# TH555-MainBoard.net
KiCad netlist of a schematic drawn in EAGLE
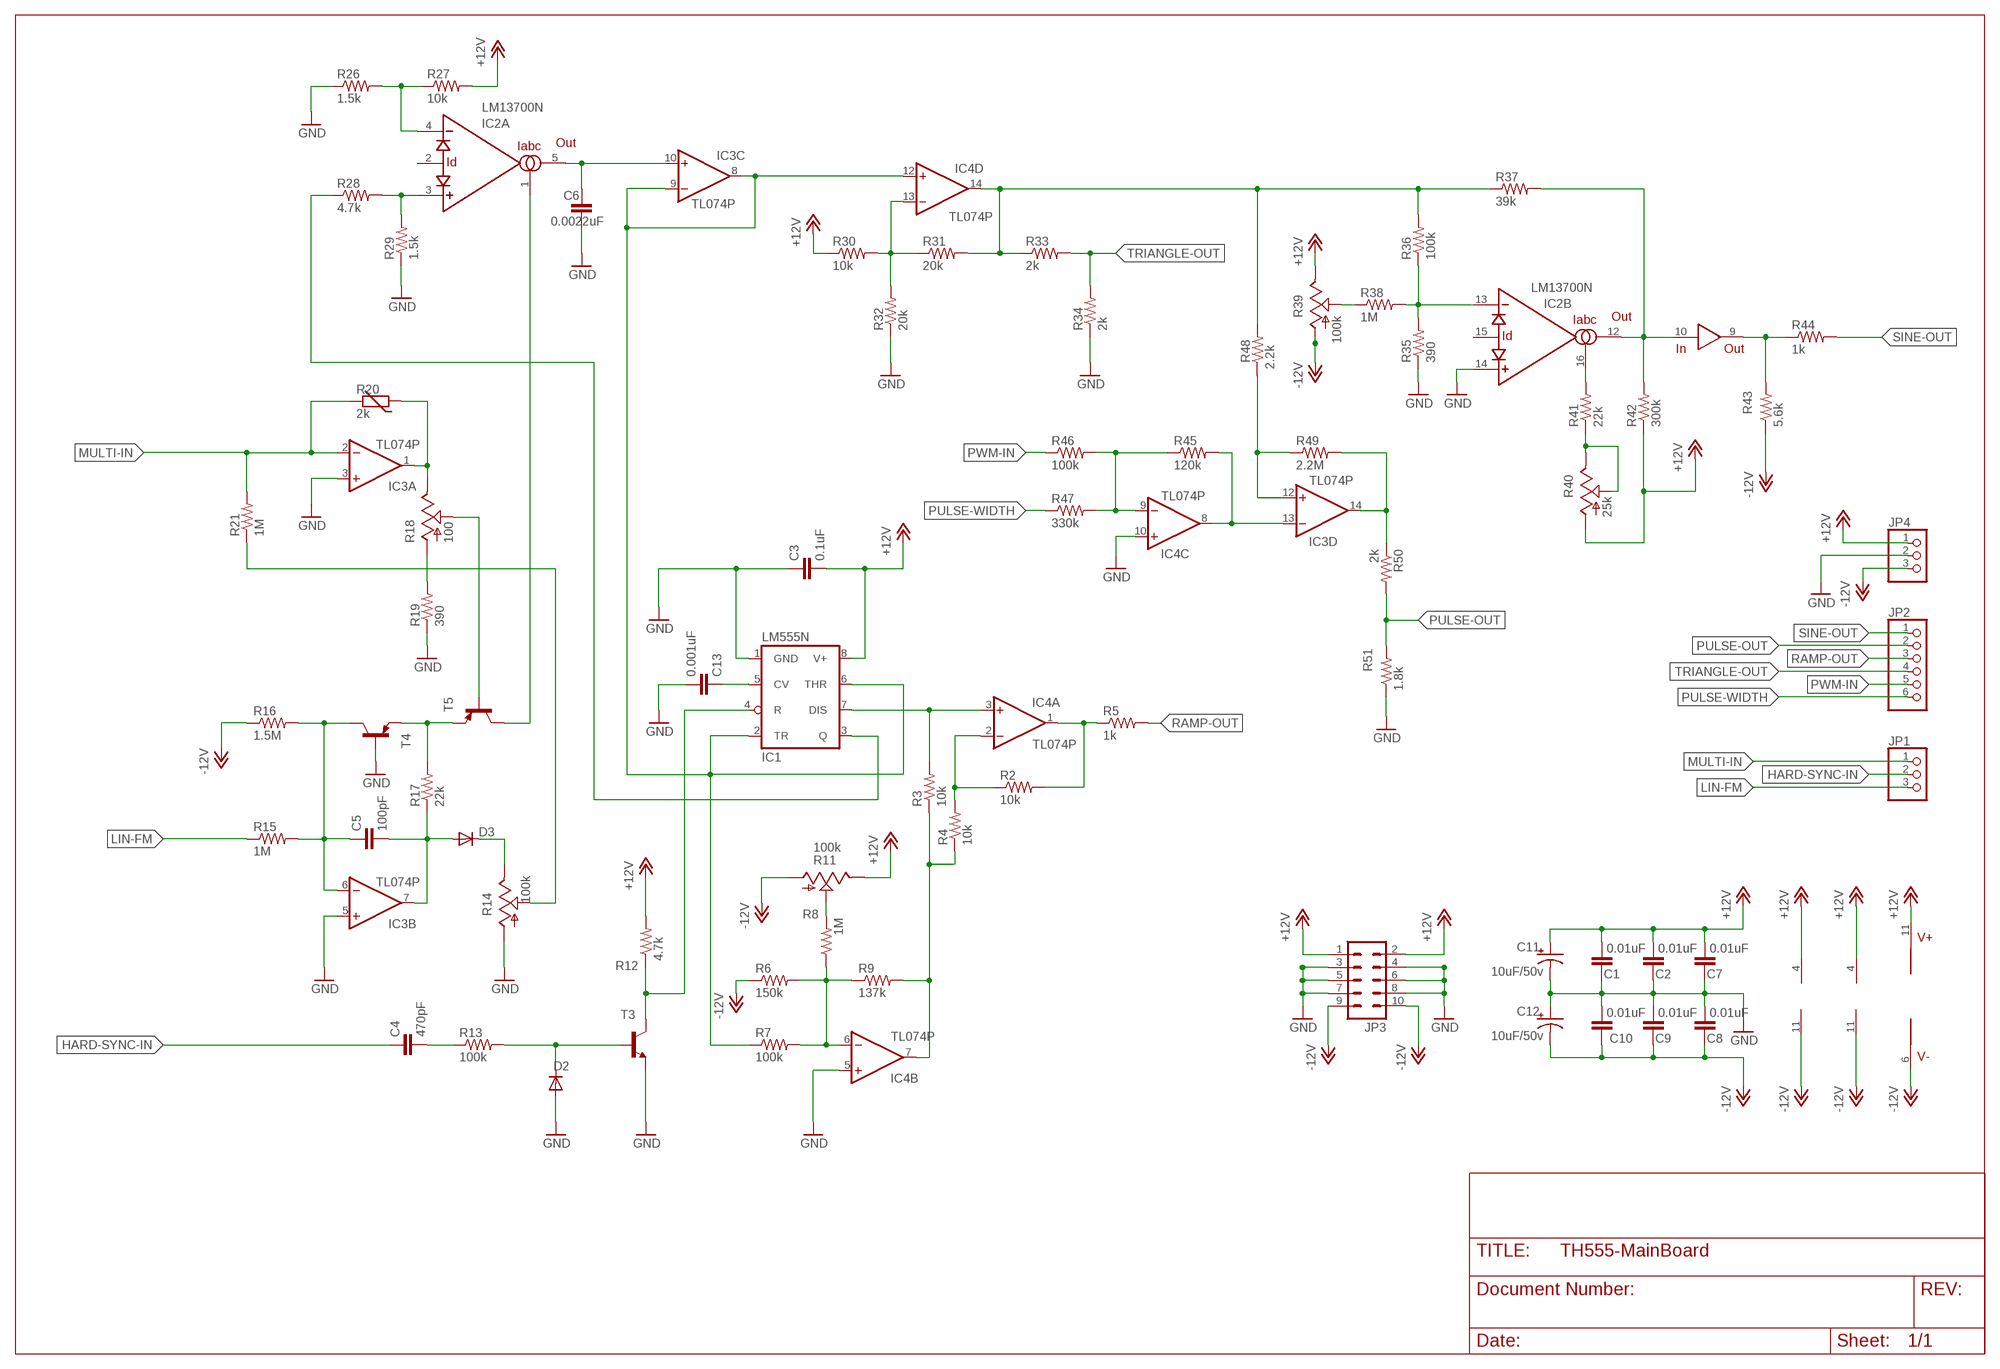
[diagram p0: schematic, sheet 1]

(export (version "E")
  (design (tool "Eeschema 10.0.6"))
  (components
    (comp (ref "C1")
      (value "0.01uF")
      (footprint "eagle-import:C050-024X044")
      (libsource (lib "eagle-import") (part "C-EU050-024X044"))
    )
    (comp (ref "C2")
      (value "0.01uF")
      (footprint "eagle-import:C050-024X044")
      (libsource (lib "eagle-import") (part "C-EU050-024X044"))
    )
    (comp (ref "C3")
      (value "0.1uF")
      (footprint "eagle-import:C050-024X044")
      (libsource (lib "eagle-import") (part "C-EU050-024X044"))
    )
    (comp (ref "C4")
      (value "470pF")
      (footprint "eagle-import:C050-024X044")
      (libsource (lib "eagle-import") (part "C-EU050-024X044"))
    )
    (comp (ref "C5")
      (value "100pF")
      (footprint "eagle-import:C050-024X044")
      (libsource (lib "eagle-import") (part "C-EU050-024X044"))
    )
    (comp (ref "C6")
      (value "0.0022uF")
      (footprint "eagle-import:C050-025X075")
      (libsource (lib "eagle-import") (part "C-EU050-025X075"))
    )
    (comp (ref "C7")
      (value "0.01uF")
      (footprint "eagle-import:C050-024X044")
      (libsource (lib "eagle-import") (part "C-EU050-024X044"))
    )
    (comp (ref "C8")
      (value "0.01uF")
      (footprint "eagle-import:C050-024X044")
      (libsource (lib "eagle-import") (part "C-EU050-024X044"))
    )
    (comp (ref "C9")
      (value "0.01uF")
      (footprint "eagle-import:C050-024X044")
      (libsource (lib "eagle-import") (part "C-EU050-024X044"))
    )
    (comp (ref "C10")
      (value "0.01uF")
      (footprint "eagle-import:C050-024X044")
      (libsource (lib "eagle-import") (part "C-EU050-024X044"))
    )
    (comp (ref "C11")
      (value "10uF/50v")
      (footprint "eagle-import:E2,5-6")
      (libsource (lib "eagle-import") (part "CPOL-USE2.5-6"))
    )
    (comp (ref "C12")
      (value "10uF/50v")
      (footprint "eagle-import:E2,5-6")
      (libsource (lib "eagle-import") (part "CPOL-USE2.5-6"))
    )
    (comp (ref "C13")
      (value "0.001uF")
      (footprint "eagle-import:C050-024X044")
      (libsource (lib "eagle-import") (part "C-EU050-024X044"))
    )
    (comp (ref "D2")
      (value "1N4148DO35-7")
      (footprint "eagle-import:DO35-7")
      (libsource (lib "eagle-import") (part "1N4148DO35-7"))
    )
    (comp (ref "D3")
      (value "1N4148DO35-7")
      (footprint "eagle-import:DO35-7")
      (libsource (lib "eagle-import") (part "1N4148DO35-7"))
    )
    (comp (ref "IC1")
      (value "LM555N")
      (footprint "eagle-import:DIL08")
      (libsource (lib "eagle-import") (part "555NLM"))
    )
    (comp (ref "IC2")
      (value "LM13700N")
      (footprint "eagle-import:DIL16")
      (libsource (lib "eagle-import") (part "LM13700N"))
    )
    (comp (ref "IC3")
      (value "TL074P")
      (footprint "eagle-import:DIL14")
      (libsource (lib "eagle-import") (part "TL074P"))
    )
    (comp (ref "IC4")
      (value "TL074P")
      (footprint "eagle-import:DIL14")
      (libsource (lib "eagle-import") (part "TL074P"))
    )
    (comp (ref "JP1")
      (value "PINHD-1X3")
      (footprint "eagle-import:1X03")
      (libsource (lib "eagle-import") (part "PINHD-1X3"))
    )
    (comp (ref "JP2")
      (value "PINHD-1X6")
      (footprint "eagle-import:1X06")
      (libsource (lib "eagle-import") (part "PINHD-1X6"))
    )
    (comp (ref "JP3")
      (value "ML10")
      (footprint "eagle-import:ML10")
      (libsource (lib "eagle-import") (part "ML10"))
    )
    (comp (ref "JP4")
      (value "PINHD-1X3")
      (footprint "eagle-import:1X03")
      (libsource (lib "eagle-import") (part "PINHD-1X3"))
    )
    (comp (ref "R2")
      (value "10k")
      (footprint "eagle-import:0204_7")
      (libsource (lib "eagle-import") (part "R-US_0204/7"))
    )
    (comp (ref "R3")
      (value "10k")
      (footprint "eagle-import:0204_7")
      (libsource (lib "eagle-import") (part "R-US_0204/7"))
    )
    (comp (ref "R4")
      (value "10k")
      (footprint "eagle-import:0204_7")
      (libsource (lib "eagle-import") (part "R-US_0204/7"))
    )
    (comp (ref "R5")
      (value "1k")
      (footprint "eagle-import:0204_7")
      (libsource (lib "eagle-import") (part "R-US_0204/7"))
    )
    (comp (ref "R6")
      (value "150k")
      (footprint "eagle-import:0204_7")
      (libsource (lib "eagle-import") (part "R-US_0204/7"))
    )
    (comp (ref "R7")
      (value "100k")
      (footprint "eagle-import:0204_7")
      (libsource (lib "eagle-import") (part "R-US_0204/7"))
    )
    (comp (ref "R8")
      (value "1M")
      (footprint "eagle-import:0204_7")
      (libsource (lib "eagle-import") (part "R-US_0204/7"))
    )
    (comp (ref "R9")
      (value "137k")
      (footprint "eagle-import:0204_7")
      (libsource (lib "eagle-import") (part "R-US_0204/7"))
    )
    (comp (ref "R11")
      (value "100k")
      (footprint "eagle-import:RJ9W")
      (libsource (lib "eagle-import") (part "TRIM_US-RJ9W"))
    )
    (comp (ref "R12")
      (value "4.7k")
      (footprint "eagle-import:0204_7")
      (libsource (lib "eagle-import") (part "R-US_0204/7"))
    )
    (comp (ref "R13")
      (value "100k")
      (footprint "eagle-import:0204_7")
      (libsource (lib "eagle-import") (part "R-US_0204/7"))
    )
    (comp (ref "R14")
      (value "100k")
      (footprint "eagle-import:RJ9W")
      (libsource (lib "eagle-import") (part "TRIM_US-RJ9W"))
    )
    (comp (ref "R15")
      (value "1M")
      (footprint "eagle-import:0204_7")
      (libsource (lib "eagle-import") (part "R-US_0204/7"))
    )
    (comp (ref "R16")
      (value "1.5M")
      (footprint "eagle-import:0204_7")
      (libsource (lib "eagle-import") (part "R-US_0204/7"))
    )
    (comp (ref "R17")
      (value "22k")
      (footprint "eagle-import:0204_7")
      (libsource (lib "eagle-import") (part "R-US_0204/7"))
    )
    (comp (ref "R18")
      (value "100")
      (footprint "eagle-import:RJ9W")
      (libsource (lib "eagle-import") (part "TRIM_US-RJ9W"))
    )
    (comp (ref "R19")
      (value "390")
      (footprint "eagle-import:0204_7")
      (libsource (lib "eagle-import") (part "R-US_0204/7"))
    )
    (comp (ref "R20")
      (value "2k")
      (footprint "eagle-import:R-5")
      (libsource (lib "eagle-import") (part "THERMISTOR-5"))
    )
    (comp (ref "R21")
      (value "1M")
      (footprint "eagle-import:0204_7")
      (libsource (lib "eagle-import") (part "R-US_0204/7"))
    )
    (comp (ref "R26")
      (value "1.5k")
      (footprint "eagle-import:0204_7")
      (libsource (lib "eagle-import") (part "R-US_0204/7"))
    )
    (comp (ref "R27")
      (value "10k")
      (footprint "eagle-import:0204_7")
      (libsource (lib "eagle-import") (part "R-US_0204/7"))
    )
    (comp (ref "R28")
      (value "4.7k")
      (footprint "eagle-import:0204_7")
      (libsource (lib "eagle-import") (part "R-US_0204/7"))
    )
    (comp (ref "R29")
      (value "1.5k")
      (footprint "eagle-import:0204_7")
      (libsource (lib "eagle-import") (part "R-US_0204/7"))
    )
    (comp (ref "R30")
      (value "10k")
      (footprint "eagle-import:0204_7")
      (libsource (lib "eagle-import") (part "R-US_0204/7"))
    )
    (comp (ref "R31")
      (value "20k")
      (footprint "eagle-import:0204_7")
      (libsource (lib "eagle-import") (part "R-US_0204/7"))
    )
    (comp (ref "R32")
      (value "20k")
      (footprint "eagle-import:0204_7")
      (libsource (lib "eagle-import") (part "R-US_0204/7"))
    )
    (comp (ref "R33")
      (value "2k")
      (footprint "eagle-import:0204_7")
      (libsource (lib "eagle-import") (part "R-US_0204/7"))
    )
    (comp (ref "R34")
      (value "2k")
      (footprint "eagle-import:0204_7")
      (libsource (lib "eagle-import") (part "R-US_0204/7"))
    )
    (comp (ref "R35")
      (value "390")
      (footprint "eagle-import:0204_7")
      (libsource (lib "eagle-import") (part "R-US_0204/7"))
    )
    (comp (ref "R36")
      (value "100k")
      (footprint "eagle-import:0204_7")
      (libsource (lib "eagle-import") (part "R-US_0204/7"))
    )
    (comp (ref "R37")
      (value "39k")
      (footprint "eagle-import:0204_7")
      (libsource (lib "eagle-import") (part "R-US_0204/7"))
    )
    (comp (ref "R38")
      (value "1M")
      (footprint "eagle-import:0204_7")
      (libsource (lib "eagle-import") (part "R-US_0204/7"))
    )
    (comp (ref "R39")
      (value "100k")
      (footprint "eagle-import:RJ9W")
      (libsource (lib "eagle-import") (part "TRIM_US-RJ9W"))
    )
    (comp (ref "R40")
      (value "25k")
      (footprint "eagle-import:RJ9W")
      (libsource (lib "eagle-import") (part "TRIM_US-RJ9W"))
    )
    (comp (ref "R41")
      (value "22k")
      (footprint "eagle-import:0204_7")
      (libsource (lib "eagle-import") (part "R-US_0204/7"))
    )
    (comp (ref "R42")
      (value "300k")
      (footprint "eagle-import:0204_7")
      (libsource (lib "eagle-import") (part "R-US_0204/7"))
    )
    (comp (ref "R43")
      (value "5.6k")
      (footprint "eagle-import:0204_7")
      (libsource (lib "eagle-import") (part "R-US_0204/7"))
    )
    (comp (ref "R44")
      (value "1k")
      (footprint "eagle-import:0204_7")
      (libsource (lib "eagle-import") (part "R-US_0204/7"))
    )
    (comp (ref "R45")
      (value "120k")
      (footprint "eagle-import:0204_7")
      (libsource (lib "eagle-import") (part "R-US_0204/7"))
    )
    (comp (ref "R46")
      (value "100k")
      (footprint "eagle-import:0204_7")
      (libsource (lib "eagle-import") (part "R-US_0204/7"))
    )
    (comp (ref "R47")
      (value "330k")
      (footprint "eagle-import:0204_7")
      (libsource (lib "eagle-import") (part "R-US_0204/7"))
    )
    (comp (ref "R48")
      (value "2.2k")
      (footprint "eagle-import:0204_7")
      (libsource (lib "eagle-import") (part "R-US_0204/7"))
    )
    (comp (ref "R49")
      (value "2.2M")
      (footprint "eagle-import:0204_7")
      (libsource (lib "eagle-import") (part "R-US_0204/7"))
    )
    (comp (ref "R50")
      (value "2k")
      (footprint "eagle-import:0204_7")
      (libsource (lib "eagle-import") (part "R-US_0204/7"))
    )
    (comp (ref "R51")
      (value "1.8k")
      (footprint "eagle-import:0204_7")
      (libsource (lib "eagle-import") (part "R-US_0204/7"))
    )
    (comp (ref "T3")
      (value "2N3904-NPN-TO92-EBC")
      (footprint "eagle-import:TO92-EBC")
      (libsource (lib "eagle-import") (part "-NPN-TO92-EBC2N3904"))
    )
    (comp (ref "T4")
      (value "2N3906-PNP-TO92-EBC")
      (footprint "eagle-import:TO92-EBC")
      (libsource (lib "eagle-import") (part "-PNP-TO92-EBC2N3906"))
    )
    (comp (ref "T5")
      (value "2N3906-PNP-TO92-EBC")
      (footprint "eagle-import:TO92-EBC")
      (libsource (lib "eagle-import") (part "-PNP-TO92-EBC2N3906"))
    )
  )
  (nets
    (net (code "1") (name "+12V") (class "Default")
      (node (ref "C1") (pin "2") (pinfunction "2_2") (pintype "passive"))
      (node (ref "C11") (pin "+") (pinfunction "+_+") (pintype "passive"))
      (node (ref "C2") (pin "2") (pinfunction "2_2") (pintype "passive"))
      (node (ref "C3") (pin "2") (pinfunction "2_2") (pintype "passive"))
      (node (ref "C7") (pin "2") (pinfunction "2_2") (pintype "passive"))
      (node (ref "IC1") (pin "8") (pinfunction "V+_8") (pintype "power_in"))
      (node (ref "IC2") (pin "11") (pinfunction "V+_11") (pintype "bidirectional"))
      (node (ref "IC3") (pin "4") (pinfunction "V+_4") (pintype "power_in"))
      (node (ref "IC4") (pin "4") (pinfunction "V+_4") (pintype "power_in"))
      (node (ref "JP3") (pin "1") (pinfunction "1_1") (pintype "passive"))
      (node (ref "JP3") (pin "2") (pinfunction "2_2") (pintype "passive"))
      (node (ref "JP4") (pin "1") (pinfunction "1_1") (pintype "passive"))
      (node (ref "R11") (pin "E") (pinfunction "E_E") (pintype "passive"))
      (node (ref "R12") (pin "2") (pinfunction "2_2") (pintype "passive"))
      (node (ref "R27") (pin "2") (pinfunction "2_2") (pintype "passive"))
      (node (ref "R30") (pin "1") (pinfunction "1_1") (pintype "passive"))
      (node (ref "R39") (pin "E") (pinfunction "E_E") (pintype "passive"))
      (node (ref "R40") (pin "A") (pinfunction "A_A") (pintype "passive"))
      (node (ref "R42") (pin "1") (pinfunction "1_1") (pintype "passive"))
    )
    (net (code "2") (name "-12V") (class "Default")
      (node (ref "C10") (pin "1") (pinfunction "1_1") (pintype "passive"))
      (node (ref "C12") (pin "-") (pinfunction "-_-") (pintype "passive"))
      (node (ref "C8") (pin "1") (pinfunction "1_1") (pintype "passive"))
      (node (ref "C9") (pin "1") (pinfunction "1_1") (pintype "passive"))
      (node (ref "IC2") (pin "6") (pinfunction "V-_6") (pintype "bidirectional"))
      (node (ref "IC3") (pin "11") (pinfunction "V-_11") (pintype "power_in"))
      (node (ref "IC4") (pin "11") (pinfunction "V-_11") (pintype "power_in"))
      (node (ref "JP3") (pin "10") (pinfunction "10_10") (pintype "passive"))
      (node (ref "JP3") (pin "9") (pinfunction "9_9") (pintype "passive"))
      (node (ref "JP4") (pin "3") (pinfunction "3_3") (pintype "passive"))
      (node (ref "R11") (pin "A") (pinfunction "A_A") (pintype "passive"))
      (node (ref "R16") (pin "1") (pinfunction "1_1") (pintype "passive"))
      (node (ref "R39") (pin "A") (pinfunction "A_A") (pintype "passive"))
      (node (ref "R43") (pin "1") (pinfunction "1_1") (pintype "passive"))
      (node (ref "R6") (pin "1") (pinfunction "1_1") (pintype "passive"))
    )
    (net (code "3") (name "GND") (class "Default")
      (node (ref "C1") (pin "1") (pinfunction "1_1") (pintype "passive"))
      (node (ref "C10") (pin "2") (pinfunction "2_2") (pintype "passive"))
      (node (ref "C11") (pin "-") (pinfunction "-_-") (pintype "passive"))
      (node (ref "C12") (pin "+") (pinfunction "+_+") (pintype "passive"))
      (node (ref "C13") (pin "1") (pinfunction "1_1") (pintype "passive"))
      (node (ref "C2") (pin "1") (pinfunction "1_1") (pintype "passive"))
      (node (ref "C3") (pin "1") (pinfunction "1_1") (pintype "passive"))
      (node (ref "C6") (pin "2") (pinfunction "2_2") (pintype "passive"))
      (node (ref "C7") (pin "1") (pinfunction "1_1") (pintype "passive"))
      (node (ref "C8") (pin "2") (pinfunction "2_2") (pintype "passive"))
      (node (ref "C9") (pin "2") (pinfunction "2_2") (pintype "passive"))
      (node (ref "D2") (pin "A") (pinfunction "A_A") (pintype "passive"))
      (node (ref "IC1") (pin "1") (pinfunction "GND_1") (pintype "power_in"))
      (node (ref "IC2") (pin "14") (pinfunction "+IN_14") (pintype "bidirectional"))
      (node (ref "IC3") (pin "3") (pinfunction "+IN_3") (pintype "input"))
      (node (ref "IC3") (pin "5") (pinfunction "+IN_5") (pintype "input"))
      (node (ref "IC4") (pin "10") (pinfunction "+IN_10") (pintype "input"))
      (node (ref "IC4") (pin "5") (pinfunction "+IN_5") (pintype "input"))
      (node (ref "JP3") (pin "3") (pinfunction "3_3") (pintype "passive"))
      (node (ref "JP3") (pin "4") (pinfunction "4_4") (pintype "passive"))
      (node (ref "JP3") (pin "5") (pinfunction "5_5") (pintype "passive"))
      (node (ref "JP3") (pin "6") (pinfunction "6_6") (pintype "passive"))
      (node (ref "JP3") (pin "7") (pinfunction "7_7") (pintype "passive"))
      (node (ref "JP3") (pin "8") (pinfunction "8_8") (pintype "passive"))
      (node (ref "JP4") (pin "2") (pinfunction "2_2") (pintype "passive"))
      (node (ref "R14") (pin "A") (pinfunction "A_A") (pintype "passive"))
      (node (ref "R19") (pin "1") (pinfunction "1_1") (pintype "passive"))
      (node (ref "R26") (pin "1") (pinfunction "1_1") (pintype "passive"))
      (node (ref "R29") (pin "1") (pinfunction "1_1") (pintype "passive"))
      (node (ref "R32") (pin "1") (pinfunction "1_1") (pintype "passive"))
      (node (ref "R34") (pin "1") (pinfunction "1_1") (pintype "passive"))
      (node (ref "R35") (pin "1") (pinfunction "1_1") (pintype "passive"))
      (node (ref "R51") (pin "1") (pinfunction "1_1") (pintype "passive"))
      (node (ref "T3") (pin "E") (pinfunction "E_E") (pintype "passive"))
      (node (ref "T4") (pin "B") (pinfunction "B_B") (pintype "passive"))
    )
    (net (code "4") (name "HARD-SYNC-IN") (class "Default")
      (node (ref "C4") (pin "1") (pinfunction "1_1") (pintype "passive"))
      (node (ref "JP1") (pin "2") (pinfunction "2_2") (pintype "passive"))
    )
    (net (code "5") (name "LIN-FM") (class "Default")
      (node (ref "JP1") (pin "3") (pinfunction "3_3") (pintype "passive"))
      (node (ref "R15") (pin "1") (pinfunction "1_1") (pintype "passive"))
    )
    (net (code "6") (name "MULTI-IN") (class "Default")
      (node (ref "IC3") (pin "2") (pinfunction "-IN_2") (pintype "input"))
      (node (ref "JP1") (pin "1") (pinfunction "1_1") (pintype "passive"))
      (node (ref "R20") (pin "2") (pinfunction "2_2") (pintype "passive"))
      (node (ref "R21") (pin "2") (pinfunction "2_2") (pintype "passive"))
    )
    (net (code "7") (name "Net-(C4-Pad2)") (class "Default")
      (node (ref "C4") (pin "2") (pinfunction "2_2") (pintype "passive"))
      (node (ref "R13") (pin "1") (pinfunction "1_1") (pintype "passive"))
    )
    (net (code "8") (name "Net-(D2-PadC)") (class "Default")
      (node (ref "D2") (pin "C") (pinfunction "C_C") (pintype "passive"))
      (node (ref "R13") (pin "2") (pinfunction "2_2") (pintype "passive"))
      (node (ref "T3") (pin "B") (pinfunction "B_B") (pintype "passive"))
    )
    (net (code "9") (name "Net-(D3-PadC)") (class "Default")
      (node (ref "D3") (pin "C") (pinfunction "C_C") (pintype "passive"))
      (node (ref "R14") (pin "E") (pinfunction "E_E") (pintype "passive"))
    )
    (net (code "10") (name "Net-(IC1-CV)") (class "Default")
      (node (ref "C13") (pin "2") (pinfunction "2_2") (pintype "passive"))
      (node (ref "IC1") (pin "5") (pinfunction "CV_5") (pintype "input"))
    )
    (net (code "11") (name "Net-(IC1-DIS)") (class "Default")
      (node (ref "IC1") (pin "7") (pinfunction "DIS_7") (pintype "input"))
      (node (ref "IC4") (pin "3") (pinfunction "+IN_3") (pintype "input"))
      (node (ref "R3") (pin "2") (pinfunction "2_2") (pintype "passive"))
    )
    (net (code "12") (name "Net-(IC1-Q)") (class "Default")
      (node (ref "IC1") (pin "3") (pinfunction "Q_3") (pintype "output"))
      (node (ref "R28") (pin "1") (pinfunction "1_1") (pintype "passive"))
    )
    (net (code "13") (name "Net-(IC1-R)") (class "Default")
      (node (ref "IC1") (pin "4") (pinfunction "R_4") (pintype "input"))
      (node (ref "R12") (pin "1") (pinfunction "1_1") (pintype "passive"))
      (node (ref "T3") (pin "C") (pinfunction "C_C") (pintype "passive"))
    )
    (net (code "14") (name "Net-(IC1-THR)") (class "Default")
      (node (ref "IC1") (pin "2") (pinfunction "TR_2") (pintype "input"))
      (node (ref "IC1") (pin "6") (pinfunction "THR_6") (pintype "input"))
      (node (ref "IC3") (pin "8") (pinfunction "OUT_8") (pintype "output"))
      (node (ref "IC3") (pin "9") (pinfunction "-IN_9") (pintype "input"))
      (node (ref "IC4") (pin "12") (pinfunction "+IN_12") (pintype "input"))
      (node (ref "R7") (pin "1") (pinfunction "1_1") (pintype "passive"))
    )
    (net (code "15") (name "Net-(IC2A-+IN)") (class "Default")
      (node (ref "IC2") (pin "3") (pinfunction "+IN_3") (pintype "bidirectional"))
      (node (ref "R28") (pin "2") (pinfunction "2_2") (pintype "passive"))
      (node (ref "R29") (pin "2") (pinfunction "2_2") (pintype "passive"))
    )
    (net (code "16") (name "Net-(IC2A--IN)") (class "Default")
      (node (ref "IC2") (pin "4") (pinfunction "-IN_4") (pintype "bidirectional"))
      (node (ref "R26") (pin "2") (pinfunction "2_2") (pintype "passive"))
      (node (ref "R27") (pin "1") (pinfunction "1_1") (pintype "passive"))
    )
    (net (code "17") (name "Net-(IC2A-IABC)") (class "Default")
      (node (ref "IC2") (pin "1") (pinfunction "IABC_1") (pintype "bidirectional"))
      (node (ref "T5") (pin "C") (pinfunction "C_C") (pintype "passive"))
    )
    (net (code "18") (name "Net-(IC2A-OUT)") (class "Default")
      (node (ref "C6") (pin "1") (pinfunction "1_1") (pintype "passive"))
      (node (ref "IC2") (pin "5") (pinfunction "OUT_5") (pintype "bidirectional"))
      (node (ref "IC3") (pin "10") (pinfunction "+IN_10") (pintype "input"))
    )
    (net (code "19") (name "Net-(IC2B--IN)") (class "Default")
      (node (ref "IC2") (pin "13") (pinfunction "-IN_13") (pintype "bidirectional"))
      (node (ref "R35") (pin "2") (pinfunction "2_2") (pintype "passive"))
      (node (ref "R36") (pin "1") (pinfunction "1_1") (pintype "passive"))
      (node (ref "R38") (pin "2") (pinfunction "2_2") (pintype "passive"))
    )
    (net (code "20") (name "Net-(IC2B-IABC)") (class "Default")
      (node (ref "IC2") (pin "16") (pinfunction "IABC_16") (pintype "bidirectional"))
      (node (ref "R41") (pin "2") (pinfunction "2_2") (pintype "passive"))
    )
    (net (code "21") (name "Net-(IC2B-OUT)") (class "Default")
      (node (ref "IC2") (pin "10") (pinfunction "IN_10") (pintype "bidirectional"))
      (node (ref "IC2") (pin "12") (pinfunction "OUT_12") (pintype "bidirectional"))
      (node (ref "R37") (pin "2") (pinfunction "2_2") (pintype "passive"))
      (node (ref "R42") (pin "2") (pinfunction "2_2") (pintype "passive"))
    )
    (net (code "22") (name "Net-(IC2D-OUT)") (class "Default")
      (node (ref "IC2") (pin "9") (pinfunction "OUT_9") (pintype "bidirectional"))
      (node (ref "R43") (pin "2") (pinfunction "2_2") (pintype "passive"))
      (node (ref "R44") (pin "1") (pinfunction "1_1") (pintype "passive"))
    )
    (net (code "23") (name "Net-(IC3A-OUT)") (class "Default")
      (node (ref "IC3") (pin "1") (pinfunction "OUT_1") (pintype "output"))
      (node (ref "R18") (pin "E") (pinfunction "E_E") (pintype "passive"))
      (node (ref "R20") (pin "1") (pinfunction "1_1") (pintype "passive"))
    )
    (net (code "24") (name "Net-(IC3B--IN)") (class "Default")
      (node (ref "C5") (pin "1") (pinfunction "1_1") (pintype "passive"))
      (node (ref "IC3") (pin "6") (pinfunction "-IN_6") (pintype "input"))
      (node (ref "R15") (pin "2") (pinfunction "2_2") (pintype "passive"))
      (node (ref "R16") (pin "2") (pinfunction "2_2") (pintype "passive"))
      (node (ref "T4") (pin "C") (pinfunction "C_C") (pintype "passive"))
    )
    (net (code "25") (name "Net-(IC3B-OUT)") (class "Default")
      (node (ref "C5") (pin "2") (pinfunction "2_2") (pintype "passive"))
      (node (ref "D3") (pin "A") (pinfunction "A_A") (pintype "passive"))
      (node (ref "IC3") (pin "7") (pinfunction "OUT_7") (pintype "output"))
      (node (ref "R17") (pin "1") (pinfunction "1_1") (pintype "passive"))
    )
    (net (code "26") (name "Net-(IC3D-+IN)") (class "Default")
      (node (ref "IC3") (pin "12") (pinfunction "+IN_12") (pintype "input"))
      (node (ref "R48") (pin "1") (pinfunction "1_1") (pintype "passive"))
      (node (ref "R49") (pin "1") (pinfunction "1_1") (pintype "passive"))
    )
    (net (code "27") (name "Net-(IC3D--IN)") (class "Default")
      (node (ref "IC3") (pin "13") (pinfunction "-IN_13") (pintype "input"))
      (node (ref "IC4") (pin "8") (pinfunction "OUT_8") (pintype "output"))
      (node (ref "R45") (pin "2") (pinfunction "2_2") (pintype "passive"))
    )
    (net (code "28") (name "Net-(IC3D-OUT)") (class "Default")
      (node (ref "IC3") (pin "14") (pinfunction "OUT_14") (pintype "output"))
      (node (ref "R49") (pin "2") (pinfunction "2_2") (pintype "passive"))
      (node (ref "R50") (pin "1") (pinfunction "1_1") (pintype "passive"))
    )
    (net (code "29") (name "Net-(IC4A--IN)") (class "Default")
      (node (ref "IC4") (pin "2") (pinfunction "-IN_2") (pintype "input"))
      (node (ref "R2") (pin "1") (pinfunction "1_1") (pintype "passive"))
      (node (ref "R4") (pin "2") (pinfunction "2_2") (pintype "passive"))
    )
    (net (code "30") (name "Net-(IC4A-OUT)") (class "Default")
      (node (ref "IC4") (pin "1") (pinfunction "OUT_1") (pintype "output"))
      (node (ref "R2") (pin "2") (pinfunction "2_2") (pintype "passive"))
      (node (ref "R5") (pin "1") (pinfunction "1_1") (pintype "passive"))
    )
    (net (code "31") (name "Net-(IC4B--IN)") (class "Default")
      (node (ref "IC4") (pin "6") (pinfunction "-IN_6") (pintype "input"))
      (node (ref "R6") (pin "2") (pinfunction "2_2") (pintype "passive"))
      (node (ref "R7") (pin "2") (pinfunction "2_2") (pintype "passive"))
      (node (ref "R8") (pin "1") (pinfunction "1_1") (pintype "passive"))
      (node (ref "R9") (pin "1") (pinfunction "1_1") (pintype "passive"))
    )
    (net (code "32") (name "Net-(IC4B-OUT)") (class "Default")
      (node (ref "IC4") (pin "7") (pinfunction "OUT_7") (pintype "output"))
      (node (ref "R3") (pin "1") (pinfunction "1_1") (pintype "passive"))
      (node (ref "R4") (pin "1") (pinfunction "1_1") (pintype "passive"))
      (node (ref "R9") (pin "2") (pinfunction "2_2") (pintype "passive"))
    )
    (net (code "33") (name "Net-(IC4C--IN)") (class "Default")
      (node (ref "IC4") (pin "9") (pinfunction "-IN_9") (pintype "input"))
      (node (ref "R45") (pin "1") (pinfunction "1_1") (pintype "passive"))
      (node (ref "R46") (pin "2") (pinfunction "2_2") (pintype "passive"))
      (node (ref "R47") (pin "2") (pinfunction "2_2") (pintype "passive"))
    )
    (net (code "34") (name "Net-(IC4D--IN)") (class "Default")
      (node (ref "IC4") (pin "13") (pinfunction "-IN_13") (pintype "input"))
      (node (ref "R30") (pin "2") (pinfunction "2_2") (pintype "passive"))
      (node (ref "R31") (pin "1") (pinfunction "1_1") (pintype "passive"))
      (node (ref "R32") (pin "2") (pinfunction "2_2") (pintype "passive"))
    )
    (net (code "35") (name "Net-(IC4D-OUT)") (class "Default")
      (node (ref "IC4") (pin "14") (pinfunction "OUT_14") (pintype "output"))
      (node (ref "R31") (pin "2") (pinfunction "2_2") (pintype "passive"))
      (node (ref "R33") (pin "1") (pinfunction "1_1") (pintype "passive"))
      (node (ref "R36") (pin "2") (pinfunction "2_2") (pintype "passive"))
      (node (ref "R37") (pin "1") (pinfunction "1_1") (pintype "passive"))
      (node (ref "R48") (pin "2") (pinfunction "2_2") (pintype "passive"))
    )
    (net (code "36") (name "Net-(R11-PadS)") (class "Default")
      (node (ref "R11") (pin "S") (pinfunction "S_S") (pintype "passive"))
      (node (ref "R8") (pin "2") (pinfunction "2_2") (pintype "passive"))
    )
    (net (code "37") (name "Net-(R14-PadS)") (class "Default")
      (node (ref "R14") (pin "S") (pinfunction "S_S") (pintype "passive"))
      (node (ref "R21") (pin "1") (pinfunction "1_1") (pintype "passive"))
    )
    (net (code "38") (name "Net-(R17-Pad2)") (class "Default")
      (node (ref "R17") (pin "2") (pinfunction "2_2") (pintype "passive"))
      (node (ref "T4") (pin "E") (pinfunction "E_E") (pintype "passive"))
      (node (ref "T5") (pin "E") (pinfunction "E_E") (pintype "passive"))
    )
    (net (code "39") (name "Net-(R18-PadA)") (class "Default")
      (node (ref "R18") (pin "A") (pinfunction "A_A") (pintype "passive"))
      (node (ref "R19") (pin "2") (pinfunction "2_2") (pintype "passive"))
    )
    (net (code "40") (name "Net-(R18-PadS)") (class "Default")
      (node (ref "R18") (pin "S") (pinfunction "S_S") (pintype "passive"))
      (node (ref "T5") (pin "B") (pinfunction "B_B") (pintype "passive"))
    )
    (net (code "41") (name "Net-(R38-Pad1)") (class "Default")
      (node (ref "R38") (pin "1") (pinfunction "1_1") (pintype "passive"))
      (node (ref "R39") (pin "S") (pinfunction "S_S") (pintype "passive"))
    )
    (net (code "42") (name "Net-(R40-PadE)") (class "Default")
      (node (ref "R40") (pin "E") (pinfunction "E_E") (pintype "passive"))
      (node (ref "R40") (pin "S") (pinfunction "S_S") (pintype "passive"))
      (node (ref "R41") (pin "1") (pinfunction "1_1") (pintype "passive"))
    )
    (net (code "43") (name "PULSE-OUT") (class "Default")
      (node (ref "JP2") (pin "2") (pinfunction "2_2") (pintype "passive"))
      (node (ref "R50") (pin "2") (pinfunction "2_2") (pintype "passive"))
      (node (ref "R51") (pin "2") (pinfunction "2_2") (pintype "passive"))
    )
    (net (code "44") (name "PULSE-WIDTH") (class "Default")
      (node (ref "JP2") (pin "6") (pinfunction "6_6") (pintype "passive"))
      (node (ref "R47") (pin "1") (pinfunction "1_1") (pintype "passive"))
    )
    (net (code "45") (name "PWM-IN") (class "Default")
      (node (ref "JP2") (pin "5") (pinfunction "5_5") (pintype "passive"))
      (node (ref "R46") (pin "1") (pinfunction "1_1") (pintype "passive"))
    )
    (net (code "46") (name "RAMP-OUT") (class "Default")
      (node (ref "JP2") (pin "3") (pinfunction "3_3") (pintype "passive"))
      (node (ref "R5") (pin "2") (pinfunction "2_2") (pintype "passive"))
    )
    (net (code "47") (name "SINE-OUT") (class "Default")
      (node (ref "JP2") (pin "1") (pinfunction "1_1") (pintype "passive"))
      (node (ref "R44") (pin "2") (pinfunction "2_2") (pintype "passive"))
    )
    (net (code "48") (name "TRIANGLE-OUT") (class "Default")
      (node (ref "JP2") (pin "4") (pinfunction "4_4") (pintype "passive"))
      (node (ref "R33") (pin "2") (pinfunction "2_2") (pintype "passive"))
      (node (ref "R34") (pin "2") (pinfunction "2_2") (pintype "passive"))
    )
    (net (code "49") (name "unconnected-(IC2A-ID-Pad2)") (class "Default")
      (node (ref "IC2") (pin "2") (pinfunction "ID_2") (pintype "bidirectional"))
    )
    (net (code "50") (name "unconnected-(IC2B-ID-Pad15)") (class "Default")
      (node (ref "IC2") (pin "15") (pinfunction "ID_15") (pintype "bidirectional"))
    )
  )
)
